# TDA2822M_SMD_Version.net
KiCad netlist of a schematic drawn in EAGLE
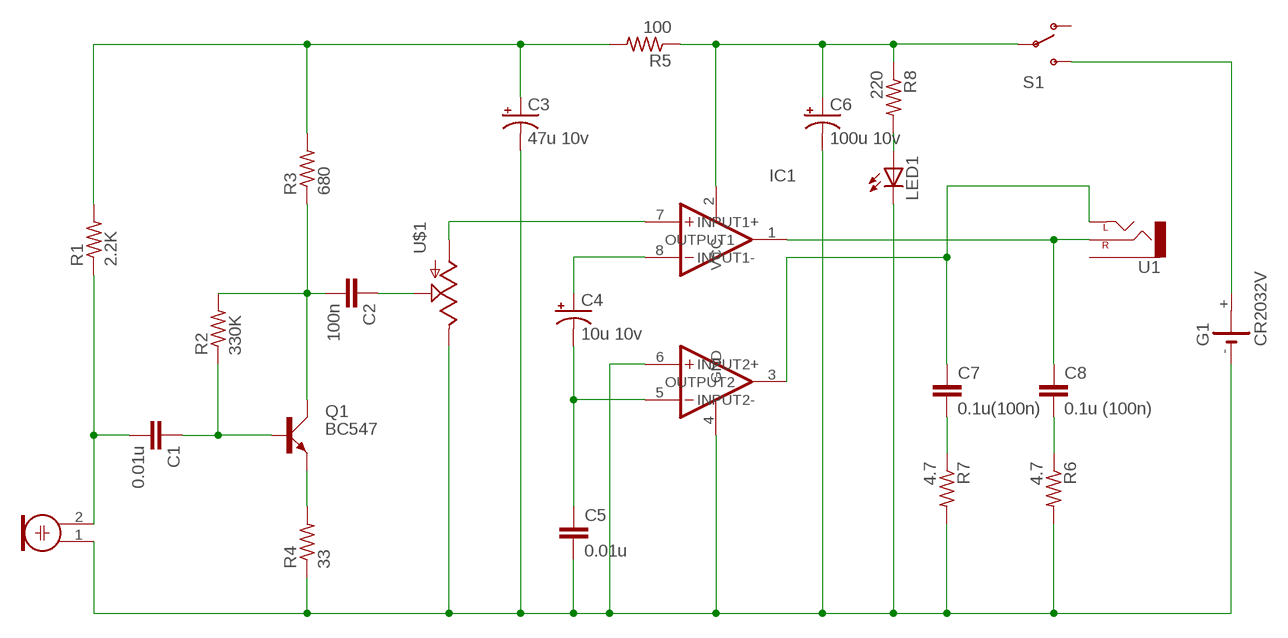
[diagram p0: schematic, sheet 1]

(export (version "E")
  (design (tool "Eeschema 10.0.6"))
  (components
    (comp (ref "C1")
      (value "0.01u")
      (footprint "eagle-import:1206")
      (libsource (lib "eagle-import") (part "CAP1206"))
    )
    (comp (ref "C2")
      (value "100n")
      (footprint "eagle-import:0805")
      (libsource (lib "eagle-import") (part "CAP0805"))
    )
    (comp (ref "C3")
      (value "47u 10v")
      (footprint "eagle-import:CPOL-RADIAL-10UF-25V")
      (libsource (lib "eagle-import") (part "CAP_POLPTH2"))
    )
    (comp (ref "C4")
      (value "10u 10v")
      (footprint "eagle-import:CPOL-RADIAL-10UF-25V")
      (libsource (lib "eagle-import") (part "CAP_POLPTH2"))
    )
    (comp (ref "C5")
      (value "0.01u")
      (footprint "eagle-import:1206")
      (libsource (lib "eagle-import") (part "CAP1206"))
    )
    (comp (ref "C6")
      (value "100u 10v")
      (footprint "eagle-import:CPOL-RADIAL-10UF-25V")
      (libsource (lib "eagle-import") (part "CAP_POLPTH2"))
    )
    (comp (ref "C7")
      (value "0.1u(100n)")
      (footprint "eagle-import:1206")
      (libsource (lib "eagle-import") (part "CAP1206"))
    )
    (comp (ref "C8")
      (value "0.1u (100n)")
      (footprint "eagle-import:1206")
      (libsource (lib "eagle-import") (part "CAP1206"))
    )
    (comp (ref "G1")
      (value "CR2032V")
      (footprint "eagle-import:CR2032V")
      (libsource (lib "eagle-import") (part "CR2032V"))
    )
    (comp (ref "IC1")
      (value "TDA2822M")
      (footprint "eagle-import:DIL8")
      (libsource (lib "eagle-import") (part "TDA2822M"))
    )
    (comp (ref "LED1")
      (value "LED3MM")
      (footprint "eagle-import:LED3MM")
      (libsource (lib "eagle-import") (part "LED3MM"))
    )
    (comp (ref "M1")
      (value "ELECTRET_MICROPHON-F6035AP")
      (footprint "eagle-import:F6035AP")
      (libsource (lib "eagle-import") (part "ELECTRET_MICROPHON-F6035AP"))
    )
    (comp (ref "Q1")
      (value "BC547")
      (footprint "eagle-import:SOT54A")
      (libsource (lib "eagle-import") (part "BC547"))
    )
    (comp (ref "R1")
      (value "2.2K")
      (footprint "eagle-import:R1206")
      (libsource (lib "eagle-import") (part "R-US_R1206"))
    )
    (comp (ref "R2")
      (value "330K")
      (footprint "eagle-import:R1206")
      (libsource (lib "eagle-import") (part "R-US_R1206"))
    )
    (comp (ref "R3")
      (value "680")
      (footprint "eagle-import:R1206")
      (libsource (lib "eagle-import") (part "R-US_R1206"))
    )
    (comp (ref "R4")
      (value "33")
      (footprint "eagle-import:R1206")
      (libsource (lib "eagle-import") (part "R-US_R1206"))
    )
    (comp (ref "R5")
      (value "100")
      (footprint "eagle-import:R1206")
      (libsource (lib "eagle-import") (part "R-US_R1206"))
    )
    (comp (ref "R6")
      (value "4.7")
      (footprint "eagle-import:R1206")
      (libsource (lib "eagle-import") (part "R-US_R1206"))
    )
    (comp (ref "R7")
      (value "4.7")
      (footprint "eagle-import:R1206")
      (libsource (lib "eagle-import") (part "R-US_R1206"))
    )
    (comp (ref "R8")
      (value "220")
      (footprint "eagle-import:R1206")
      (libsource (lib "eagle-import") (part "R-US_R1206"))
    )
    (comp (ref "S1")
      (value "SWITCH-SPSTKIT")
      (footprint "eagle-import:SWITCH-SPDT_KIT")
      (libsource (lib "eagle-import") (part "SWITCH-SPSTKIT"))
    )
    (comp (ref "U$1")
      (value "POT-RV16AF-20")
      (footprint "eagle-import:POT_ALPHA_RV16AF-20")
      (libsource (lib "eagle-import") (part "POT-RV16AF-20"))
    )
    (comp (ref "U1")
      (value "AUDIO-JACKPTH")
      (footprint "eagle-import:AUDIO-JACK")
      (libsource (lib "eagle-import") (part "AUDIO-JACKPTH"))
    )
  )
  (nets
    (net (code "1") (name "Net-(C1-Pad1)") (class "Default")
      (node (ref "C1") (pin "1") (pinfunction "1_1") (pintype "passive"))
      (node (ref "Q1") (pin "B") (pinfunction "B_B") (pintype "passive"))
      (node (ref "R2") (pin "1") (pinfunction "1_1") (pintype "passive"))
    )
    (net (code "2") (name "Net-(C1-Pad2)") (class "Default")
      (node (ref "C1") (pin "2") (pinfunction "2_2") (pintype "passive"))
      (node (ref "M1") (pin "2") (pinfunction "2_2") (pintype "passive"))
      (node (ref "R1") (pin "1") (pinfunction "1_1") (pintype "passive"))
    )
    (net (code "3") (name "Net-(C2-Pad2)") (class "Default")
      (node (ref "C2") (pin "2") (pinfunction "2_2") (pintype "passive"))
      (node (ref "Q1") (pin "C") (pinfunction "C_C") (pintype "passive"))
      (node (ref "R2") (pin "2") (pinfunction "2_2") (pintype "passive"))
      (node (ref "R3") (pin "1") (pinfunction "1_1") (pintype "passive"))
    )
    (net (code "4") (name "Net-(C3-+)") (class "Default")
      (node (ref "C3") (pin "1") (pinfunction "+_1") (pintype "passive"))
      (node (ref "R1") (pin "2") (pinfunction "2_2") (pintype "passive"))
      (node (ref "R3") (pin "2") (pinfunction "2_2") (pintype "passive"))
      (node (ref "R5") (pin "2") (pinfunction "2_2") (pintype "passive"))
    )
    (net (code "5") (name "Net-(C3--)") (class "Default")
      (node (ref "C3") (pin "2") (pinfunction "-_2") (pintype "passive"))
      (node (ref "C5") (pin "2") (pinfunction "2_2") (pintype "passive"))
      (node (ref "C6") (pin "2") (pinfunction "-_2") (pintype "passive"))
      (node (ref "G1") (pin "-") (pinfunction "-_-") (pintype "passive"))
      (node (ref "IC1") (pin "4") (pinfunction "GND_4") (pintype "bidirectional"))
      (node (ref "IC1") (pin "6") (pinfunction "INPUT2+_6") (pintype "bidirectional"))
      (node (ref "LED1") (pin "K") (pinfunction "C_K") (pintype "passive"))
      (node (ref "M1") (pin "1") (pinfunction "1_1") (pintype "passive"))
      (node (ref "R4") (pin "1") (pinfunction "1_1") (pintype "passive"))
      (node (ref "R6") (pin "2") (pinfunction "2_2") (pintype "passive"))
      (node (ref "R7") (pin "2") (pinfunction "2_2") (pintype "passive"))
      (node (ref "U$1") (pin "3") (pinfunction "E_3") (pintype "passive"))
    )
    (net (code "6") (name "Net-(C4-+)") (class "Default")
      (node (ref "C4") (pin "1") (pinfunction "+_1") (pintype "passive"))
      (node (ref "IC1") (pin "8") (pinfunction "INPUT1-_8") (pintype "bidirectional"))
    )
    (net (code "7") (name "Net-(C4--)") (class "Default")
      (node (ref "C4") (pin "2") (pinfunction "-_2") (pintype "passive"))
      (node (ref "C5") (pin "1") (pinfunction "1_1") (pintype "passive"))
      (node (ref "IC1") (pin "5") (pinfunction "INPUT2-_5") (pintype "bidirectional"))
    )
    (net (code "8") (name "Net-(C6-+)") (class "Default")
      (node (ref "C6") (pin "1") (pinfunction "+_1") (pintype "passive"))
      (node (ref "IC1") (pin "2") (pinfunction "VCC_2") (pintype "bidirectional"))
      (node (ref "R5") (pin "1") (pinfunction "1_1") (pintype "passive"))
      (node (ref "R8") (pin "1") (pinfunction "1_1") (pintype "passive"))
      (node (ref "S1") (pin "2") (pinfunction "P_2") (pintype "passive"))
    )
    (net (code "9") (name "Net-(C7-Pad2)") (class "Default")
      (node (ref "C7") (pin "2") (pinfunction "2_2") (pintype "passive"))
      (node (ref "R7") (pin "1") (pinfunction "1_1") (pintype "passive"))
    )
    (net (code "10") (name "Net-(C8-Pad2)") (class "Default")
      (node (ref "C8") (pin "2") (pinfunction "2_2") (pintype "passive"))
      (node (ref "R6") (pin "1") (pinfunction "1_1") (pintype "passive"))
    )
    (net (code "11") (name "Net-(IC1-INPUT1+)") (class "Default")
      (node (ref "IC1") (pin "7") (pinfunction "INPUT1+_7") (pintype "bidirectional"))
      (node (ref "U$1") (pin "1") (pinfunction "A_1") (pintype "passive"))
    )
    (net (code "12") (name "Net-(IC1-OUTPUT1)") (class "Default")
      (node (ref "C8") (pin "1") (pinfunction "1_1") (pintype "passive"))
      (node (ref "IC1") (pin "1") (pinfunction "OUTPUT1_1") (pintype "bidirectional"))
      (node (ref "U1") (pin "RING") (pinfunction "RIGHT_RING") (pintype "bidirectional"))
    )
    (net (code "13") (name "Net-(IC1-OUTPUT2)") (class "Default")
      (node (ref "C7") (pin "1") (pinfunction "1_1") (pintype "passive"))
      (node (ref "IC1") (pin "3") (pinfunction "OUTPUT2_3") (pintype "bidirectional"))
      (node (ref "U1") (pin "TIP") (pinfunction "LEFT_TIP") (pintype "bidirectional"))
    )
    (net (code "14") (name "Net-(LED1-PadA)") (class "Default")
      (node (ref "LED1") (pin "A") (pinfunction "A_A") (pintype "passive"))
      (node (ref "R8") (pin "2") (pinfunction "2_2") (pintype "passive"))
    )
    (net (code "15") (name "Net-(Q1-PadE)") (class "Default")
      (node (ref "Q1") (pin "E") (pinfunction "E_E") (pintype "passive"))
      (node (ref "R4") (pin "2") (pinfunction "2_2") (pintype "passive"))
    )
    (net (code "16") (name "Net-(S1-S)") (class "Default")
      (node (ref "G1") (pin "+") (pinfunction "+_+") (pintype "passive"))
      (node (ref "S1") (pin "3") (pinfunction "S_3") (pintype "passive"))
    )
    (net (code "17") (name "Net-(U$1-S)") (class "Default")
      (node (ref "C2") (pin "1") (pinfunction "1_1") (pintype "passive"))
      (node (ref "U$1") (pin "2") (pinfunction "S_2") (pintype "passive"))
    )
    (net (code "18") (name "unconnected-(G1-+-Pad+@1)") (class "Default")
      (node (ref "G1") (pin "+@1") (pinfunction "+_+@1") (pintype "passive"))
    )
    (net (code "19") (name "unconnected-(S1-O-Pad1)") (class "Default")
      (node (ref "S1") (pin "1") (pinfunction "O_1") (pintype "passive"))
    )
    (net (code "20") (name "unconnected-(U1-PadSLEEVE)") (class "Default")
      (node (ref "U1") (pin "SLEEVE") (pinfunction "SLEEVE_SLEEVE") (pintype "bidirectional"))
    )
  )
)
